# con-board-jtag.net
KiCad netlist of a schematic drawn in Altium Designer
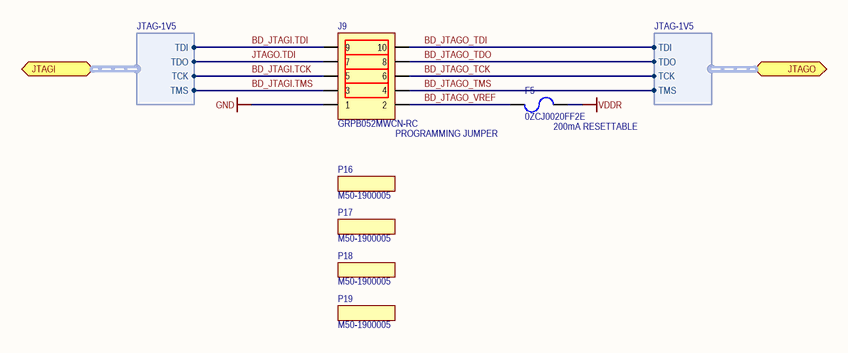
[diagram p0: con-board-jtag.SchDoc]

(export (version "E")
  (design (tool "Eeschema 10.0.6"))
  (components
    (comp (ref "F5")
      (value "0ZCJ0020FF2E")
      (footprint "generic:1206")
      (description "PTC Resettable Fuse, 0.2A, 30V, SMD 1206")
      (fields (field (name "MANUFACTURER") "Bell Fuse"))
      (libsource (lib "bel-fuse") (part "0ZCJ0020FF2E"))
    )
    (comp (ref "J9")
      (value "GRPB052MWCN-RC")
      (footprint "sullins:GRPB052MWCN")
      (description "Male Header, 0.050\" Pitch, Right Angle, 2x5 Position")
      (fields (field (name "MANUFACTURER") "Sullins"))
      (libsource (lib "sullins") (part "GRPB052MWCN-RC"))
    )
    (comp (ref "P16")
      (value "M50-1900005")
      (description "1.27mm Jumper Socket")
      (fields (field (name "MANUFACTURER") "Harwin"))
      (libsource (lib "harwin") (part "M50-1900005"))
    )
    (comp (ref "P17")
      (value "M50-1900005")
      (description "1.27mm Jumper Socket")
      (fields (field (name "MANUFACTURER") "Harwin"))
      (libsource (lib "harwin") (part "M50-1900005"))
    )
    (comp (ref "P18")
      (value "M50-1900005")
      (description "1.27mm Jumper Socket")
      (fields (field (name "MANUFACTURER") "Harwin"))
      (libsource (lib "harwin") (part "M50-1900005"))
    )
    (comp (ref "P19")
      (value "M50-1900005")
      (description "1.27mm Jumper Socket")
      (fields (field (name "MANUFACTURER") "Harwin"))
      (libsource (lib "harwin") (part "M50-1900005"))
    )
  )
  (nets
    (net (code "2") (name "/BD_JTAGI.TCK") (class "Default")
      (node (ref "J9") (pin "5") (pinfunction "5_5") (pintype "passive"))
    )
    (net (code "3") (name "/BD_JTAGI.TDI") (class "Default")
      (node (ref "J9") (pin "9") (pinfunction "9_9") (pintype "passive"))
    )
    (net (code "4") (name "/BD_JTAGI.TMS") (class "Default")
      (node (ref "J9") (pin "3") (pinfunction "3_3") (pintype "passive"))
    )
    (net (code "5") (name "/BD_JTAGO_TCK") (class "Default")
      (node (ref "J9") (pin "6") (pinfunction "6_6") (pintype "passive"))
    )
    (net (code "6") (name "/BD_JTAGO_TDI") (class "Default")
      (node (ref "J9") (pin "10") (pinfunction "10_10") (pintype "passive"))
    )
    (net (code "7") (name "/BD_JTAGO_TDO") (class "Default")
      (node (ref "J9") (pin "8") (pinfunction "8_8") (pintype "passive"))
    )
    (net (code "8") (name "/BD_JTAGO_TMS") (class "Default")
      (node (ref "J9") (pin "4") (pinfunction "4_4") (pintype "passive"))
    )
    (net (code "9") (name "/BD_JTAGO_VREF") (class "Default")
      (node (ref "F5") (pin "2") (pinfunction "2_2") (pintype "passive"))
      (node (ref "J9") (pin "2") (pinfunction "2_2") (pintype "passive"))
    )
    (net (code "10") (name "/JTAGO.TDI") (class "Default")
      (node (ref "J9") (pin "7") (pinfunction "7_7") (pintype "passive"))
    )
    (net (code "12") (name "GND") (class "Default")
      (node (ref "J9") (pin "1") (pinfunction "1_1") (pintype "passive"))
    )
    (net (code "13") (name "VDDR") (class "Default")
      (node (ref "F5") (pin "1") (pinfunction "1_1") (pintype "passive"))
    )
  )
)
